# SCHEMATIC.net
KiCad netlist of a schematic drawn in EasyEDA
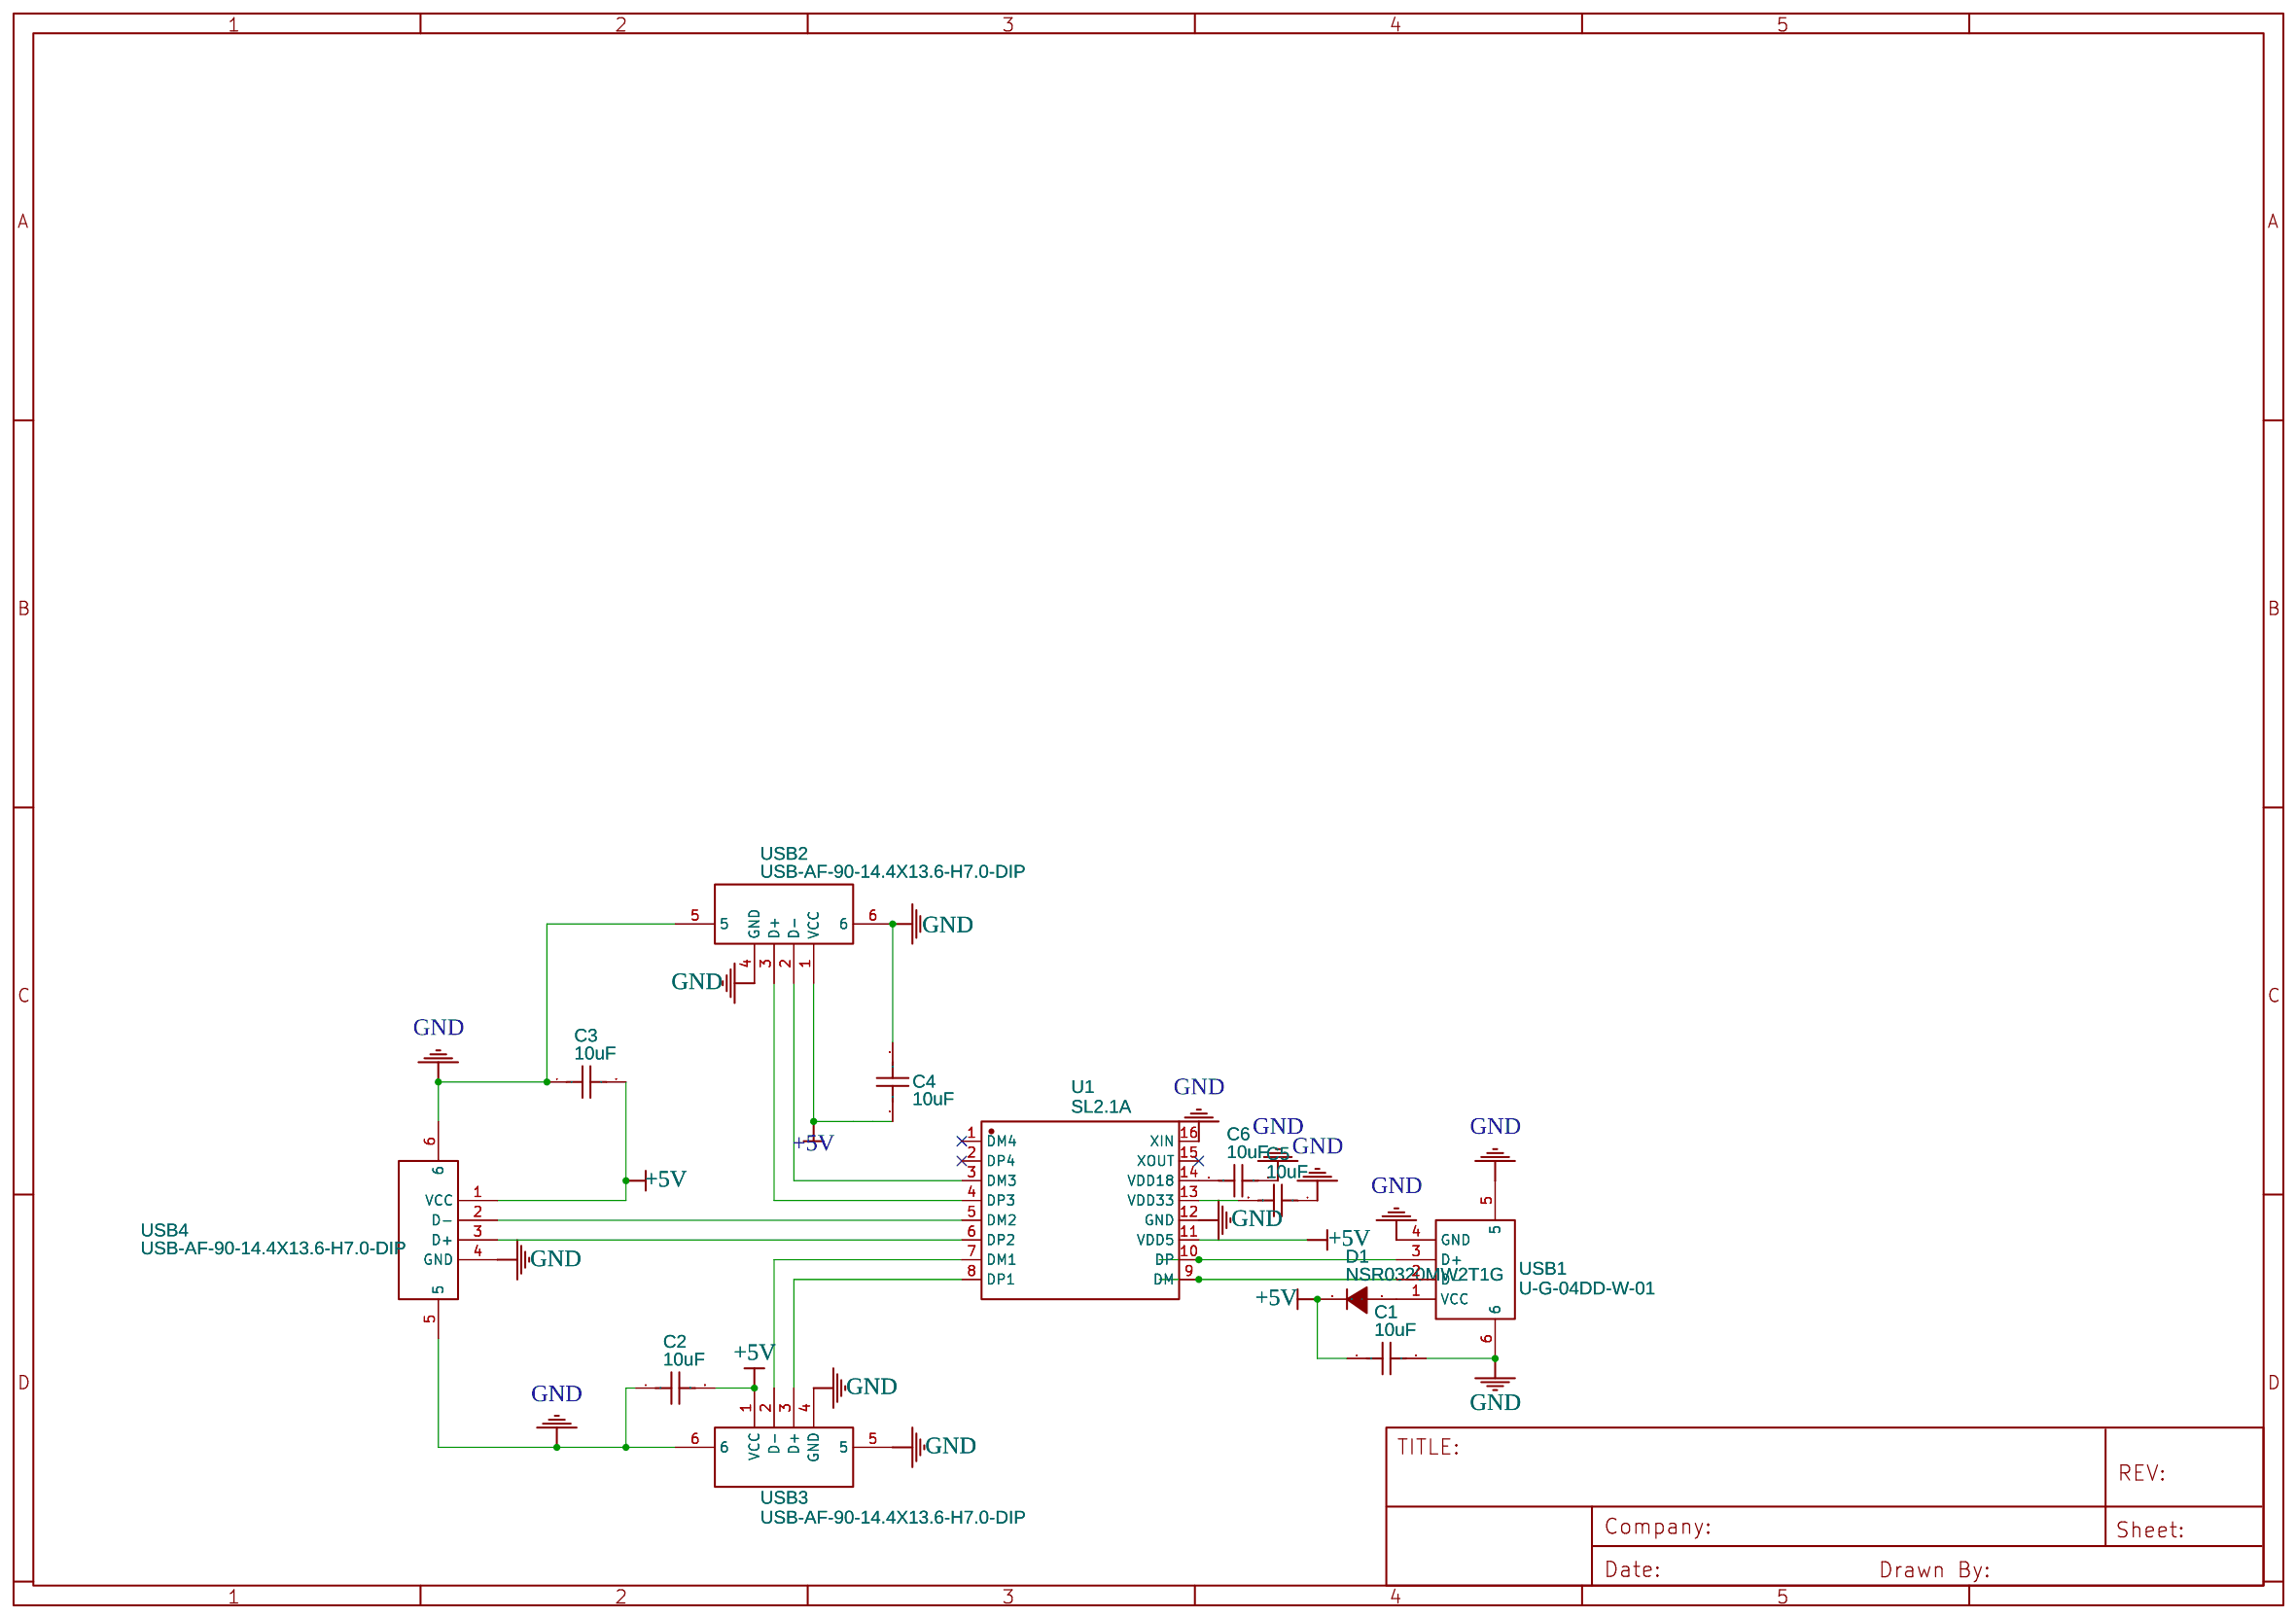
[diagram p0: schematic sheet]

(export (version "E")
  (design (tool "Eeschema 10.0.6"))
  (components
    (comp (ref "C1")
      (value "10uF")
      (fields
        (field (name "Manufacturer Part") "CL10A106KP8NNNC")
        (field (name "Manufacturer") "SAMSUNG(三星)")
      )
      (libsource (lib "") (part "CL10A106KP8NNNC_2"))
    )
    (comp (ref "C2")
      (value "10uF")
      (fields
        (field (name "Manufacturer Part") "CL10A106KP8NNNC")
        (field (name "Manufacturer") "SAMSUNG(三星)")
      )
      (libsource (lib "") (part "CL10A106KP8NNNC_2"))
    )
    (comp (ref "C3")
      (value "10uF")
      (fields
        (field (name "Manufacturer Part") "CL10A106KP8NNNC")
        (field (name "Manufacturer") "SAMSUNG(三星)")
      )
      (libsource (lib "") (part "CL10A106KP8NNNC_2"))
    )
    (comp (ref "C4")
      (value "10uF")
      (fields
        (field (name "Manufacturer Part") "CL10A106KP8NNNC")
        (field (name "Manufacturer") "SAMSUNG(三星)")
      )
      (libsource (lib "") (part "CL10A106KP8NNNC_1"))
    )
    (comp (ref "C5")
      (value "10uF")
      (fields
        (field (name "Manufacturer Part") "CL10A106KP8NNNC")
        (field (name "Manufacturer") "SAMSUNG(三星)")
      )
      (libsource (lib "") (part "CL10A106KP8NNNC"))
    )
    (comp (ref "C6")
      (value "10uF")
      (fields
        (field (name "Manufacturer Part") "CL10A106KP8NNNC")
        (field (name "Manufacturer") "SAMSUNG(三星)")
      )
      (libsource (lib "") (part "CL10A106KP8NNNC_2"))
    )
    (comp (ref "D1")
      (value "NSR0320MW2T1G")
      (fields (field (name "Manufacturer") "onsemi(安森美)"))
      (libsource (lib "") (part "NSR0320MW2T1G"))
    )
    (comp (ref "U1")
      (value "SL2.1A")
      (fields (field (name "Manufacturer") "CoreChips(和芯润德)"))
      (libsource (lib "") (part "SL2.1A"))
    )
    (comp (ref "USB1")
      (value "U-G-04DD-W-01")
      (fields (field (name "Manufacturer Part") "U-G-O4DD-W-1") (field (name "Manufacturer") "韩国韩荣"))
      (libsource (lib "") (part "U-G-04DD-W-01"))
    )
    (comp (ref "USB2")
      (value "USB-AF-90-14.4X13.6-H7.0-DIP")
      (fields (field (name "Manufacturer Part") "903-131A1011D10100") (field (name "Manufacturer") "精拓金"))
      (libsource (lib "") (part "USB-AF-90-14.4X13.6-H7.0-DIP"))
    )
    (comp (ref "USB3")
      (value "USB-AF-90-14.4X13.6-H7.0-DIP")
      (fields (field (name "Manufacturer Part") "903-131A1011D10100") (field (name "Manufacturer") "精拓金"))
      (libsource (lib "") (part "USB-AF-90-14.4X13.6-H7.0-DIP_1"))
    )
    (comp (ref "USB4")
      (value "USB-AF-90-14.4X13.6-H7.0-DIP")
      (fields (field (name "Manufacturer Part") "903-131A1011D10100") (field (name "Manufacturer") "精拓金"))
      (libsource (lib "") (part "USB-AF-90-14.4X13.6-H7.0-DIP_2"))
    )
  )
  (nets
    (net (code "1") (name "+5V") (class "Default")
      (node (ref "C1") (pin "1") (pinfunction "1_1") (pintype "unspecified"))
      (node (ref "C2") (pin "2") (pinfunction "2_2") (pintype "unspecified"))
      (node (ref "C3") (pin "2") (pinfunction "2_2") (pintype "unspecified"))
      (node (ref "C4") (pin "1") (pinfunction "1_1") (pintype "unspecified"))
      (node (ref "D1") (pin "1") (pinfunction "C_1") (pintype "unspecified"))
      (node (ref "U1") (pin "11") (pinfunction "VDD5_11") (pintype "unspecified"))
      (node (ref "USB2") (pin "1") (pinfunction "VCC_1") (pintype "unspecified"))
      (node (ref "USB3") (pin "1") (pinfunction "VCC_1") (pintype "unspecified"))
      (node (ref "USB4") (pin "1") (pinfunction "VCC_1") (pintype "unspecified"))
    )
    (net (code "2") (name "GND") (class "Default")
      (node (ref "C1") (pin "2") (pinfunction "2_2") (pintype "unspecified"))
      (node (ref "C2") (pin "1") (pinfunction "1_1") (pintype "unspecified"))
      (node (ref "C3") (pin "1") (pinfunction "1_1") (pintype "unspecified"))
      (node (ref "C4") (pin "2") (pinfunction "2_2") (pintype "unspecified"))
      (node (ref "C5") (pin "1") (pinfunction "1_1") (pintype "unspecified"))
      (node (ref "C6") (pin "2") (pinfunction "2_2") (pintype "unspecified"))
      (node (ref "U1") (pin "12") (pinfunction "GND_12") (pintype "unspecified"))
      (node (ref "U1") (pin "16") (pinfunction "XIN_16") (pintype "unspecified"))
      (node (ref "USB1") (pin "4") (pinfunction "GND_4") (pintype "unspecified"))
      (node (ref "USB1") (pin "5") (pinfunction "5_5") (pintype "unspecified"))
      (node (ref "USB1") (pin "6") (pinfunction "6_6") (pintype "unspecified"))
      (node (ref "USB2") (pin "4") (pinfunction "GND_4") (pintype "unspecified"))
      (node (ref "USB2") (pin "5") (pinfunction "5_5") (pintype "unspecified"))
      (node (ref "USB2") (pin "6") (pinfunction "6_6") (pintype "unspecified"))
      (node (ref "USB3") (pin "4") (pinfunction "GND_4") (pintype "unspecified"))
      (node (ref "USB3") (pin "5") (pinfunction "5_5") (pintype "unspecified"))
      (node (ref "USB3") (pin "6") (pinfunction "6_6") (pintype "unspecified"))
      (node (ref "USB4") (pin "4") (pinfunction "GND_4") (pintype "unspecified"))
      (node (ref "USB4") (pin "5") (pinfunction "5_5") (pintype "unspecified"))
      (node (ref "USB4") (pin "6") (pinfunction "6_6") (pintype "unspecified"))
    )
    (net (code "3") (name "Net-(D1-A)") (class "Default")
      (node (ref "D1") (pin "2") (pinfunction "A_2") (pintype "unspecified"))
      (node (ref "USB1") (pin "1") (pinfunction "VCC_1") (pintype "unspecified"))
    )
    (net (code "4") (name "Net-(U1-DM)") (class "Default")
      (node (ref "U1") (pin "9") (pinfunction "DM_9") (pintype "unspecified"))
      (node (ref "USB1") (pin "2") (pinfunction "D-_2") (pintype "unspecified"))
    )
    (net (code "5") (name "Net-(U1-DM1)") (class "Default")
      (node (ref "U1") (pin "7") (pinfunction "DM1_7") (pintype "unspecified"))
      (node (ref "USB3") (pin "2") (pinfunction "D-_2") (pintype "unspecified"))
    )
    (net (code "6") (name "Net-(U1-DM2)") (class "Default")
      (node (ref "U1") (pin "5") (pinfunction "DM2_5") (pintype "unspecified"))
      (node (ref "USB4") (pin "2") (pinfunction "D-_2") (pintype "unspecified"))
    )
    (net (code "7") (name "Net-(U1-DM3)") (class "Default")
      (node (ref "U1") (pin "3") (pinfunction "DM3_3") (pintype "unspecified"))
      (node (ref "USB2") (pin "2") (pinfunction "D-_2") (pintype "unspecified"))
    )
    (net (code "8") (name "Net-(U1-DP)") (class "Default")
      (node (ref "U1") (pin "10") (pinfunction "DP_10") (pintype "unspecified"))
      (node (ref "USB1") (pin "3") (pinfunction "D+_3") (pintype "unspecified"))
    )
    (net (code "9") (name "Net-(U1-DP1)") (class "Default")
      (node (ref "U1") (pin "8") (pinfunction "DP1_8") (pintype "unspecified"))
      (node (ref "USB3") (pin "3") (pinfunction "D+_3") (pintype "unspecified"))
    )
    (net (code "10") (name "Net-(U1-DP2)") (class "Default")
      (node (ref "U1") (pin "6") (pinfunction "DP2_6") (pintype "unspecified"))
      (node (ref "USB4") (pin "3") (pinfunction "D+_3") (pintype "unspecified"))
    )
    (net (code "11") (name "Net-(U1-DP3)") (class "Default")
      (node (ref "U1") (pin "4") (pinfunction "DP3_4") (pintype "unspecified"))
      (node (ref "USB2") (pin "3") (pinfunction "D+_3") (pintype "unspecified"))
    )
    (net (code "12") (name "Net-(U1-VDD18)") (class "Default")
      (node (ref "C6") (pin "1") (pinfunction "1_1") (pintype "unspecified"))
      (node (ref "U1") (pin "14") (pinfunction "VDD18_14") (pintype "unspecified"))
    )
    (net (code "13") (name "Net-(U1-VDD33)") (class "Default")
      (node (ref "C5") (pin "2") (pinfunction "2_2") (pintype "unspecified"))
      (node (ref "U1") (pin "13") (pinfunction "VDD33_13") (pintype "unspecified"))
    )
    (net (code "14") (name "unconnected-(U1-DM4-Pad1)") (class "Default")
      (node (ref "U1") (pin "1") (pinfunction "DM4_1") (pintype "unspecified+no_connect"))
    )
    (net (code "15") (name "unconnected-(U1-DP4-Pad2)") (class "Default")
      (node (ref "U1") (pin "2") (pinfunction "DP4_2") (pintype "unspecified+no_connect"))
    )
    (net (code "16") (name "unconnected-(U1-XOUT-Pad15)") (class "Default")
      (node (ref "U1") (pin "15") (pinfunction "XOUT_15") (pintype "unspecified+no_connect"))
    )
  )
)
